# Ex_Adafruit_I2C_Adapter.net
KiCad netlist of a schematic drawn in EAGLE
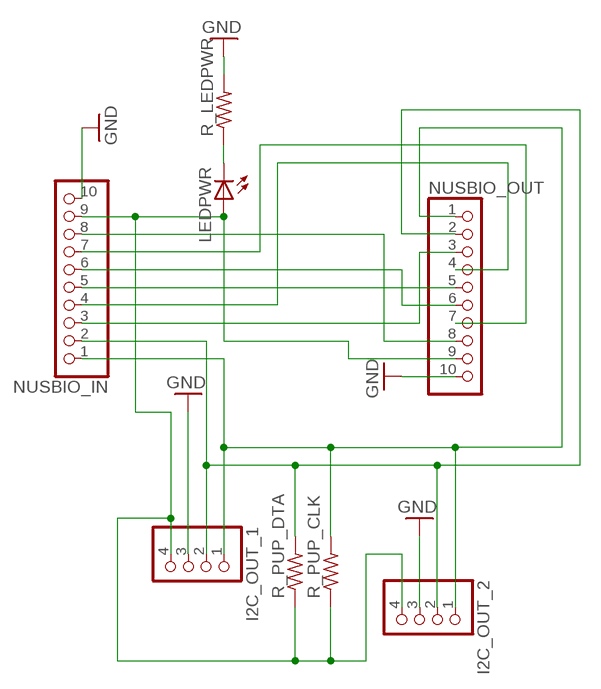
[diagram p0: schematic, sheet 1]

(export (version "E")
  (design (tool "Eeschema 10.0.6"))
  (components
    (comp (ref "I2C_OUT_1")
      (value "PINHD-1X4")
      (footprint "eagle-import:1X04")
      (libsource (lib "eagle-import") (part "PINHD-1X4"))
    )
    (comp (ref "I2C_OUT_2")
      (value "PINHD-1X4")
      (footprint "eagle-import:1X04")
      (libsource (lib "eagle-import") (part "PINHD-1X4"))
    )
    (comp (ref "LEDPWR")
      (value "LEDCHIPLED_0805")
      (footprint "eagle-import:CHIPLED_0805")
      (libsource (lib "eagle-import") (part "LEDCHIPLED_0805"))
    )
    (comp (ref "NUSBIO_IN")
      (value "PINHD-1X10")
      (footprint "eagle-import:1X10-BIG")
      (libsource (lib "eagle-import") (part "PINHD-1X10"))
    )
    (comp (ref "NUSBIO_OUT")
      (value "PINHD-1X10")
      (footprint "eagle-import:1X10-BIG")
      (libsource (lib "eagle-import") (part "PINHD-1X10"))
    )
    (comp (ref "R_LEDPWR")
      (value "R-US_R0805")
      (footprint "eagle-import:R0805")
      (libsource (lib "eagle-import") (part "R-US_R0805"))
    )
    (comp (ref "R_PUP_CLK")
      (value "R-US_R0805")
      (footprint "eagle-import:R0805")
      (libsource (lib "eagle-import") (part "R-US_R0805"))
    )
    (comp (ref "R_PUP_DTA")
      (value "R-US_R0805")
      (footprint "eagle-import:R0805")
      (libsource (lib "eagle-import") (part "R-US_R0805"))
    )
  )
  (nets
    (net (code "1") (name "GND") (class "Default")
      (node (ref "I2C_OUT_1") (pin "3") (pinfunction "3_3") (pintype "passive"))
      (node (ref "I2C_OUT_2") (pin "3") (pinfunction "3_3") (pintype "passive"))
      (node (ref "NUSBIO_IN") (pin "10") (pinfunction "10_10") (pintype "passive"))
      (node (ref "NUSBIO_OUT") (pin "10") (pinfunction "10_10") (pintype "passive"))
      (node (ref "R_LEDPWR") (pin "2") (pinfunction "2_2") (pintype "passive"))
    )
    (net (code "2") (name "Net-(I2C_OUT_1-Pad1)") (class "Default")
      (node (ref "I2C_OUT_1") (pin "1") (pinfunction "1_1") (pintype "passive"))
      (node (ref "I2C_OUT_2") (pin "1") (pinfunction "1_1") (pintype "passive"))
      (node (ref "NUSBIO_IN") (pin "1") (pinfunction "1_1") (pintype "passive"))
      (node (ref "NUSBIO_OUT") (pin "1") (pinfunction "1_1") (pintype "passive"))
      (node (ref "R_PUP_CLK") (pin "2") (pinfunction "2_2") (pintype "passive"))
    )
    (net (code "3") (name "Net-(I2C_OUT_1-Pad2)") (class "Default")
      (node (ref "I2C_OUT_1") (pin "2") (pinfunction "2_2") (pintype "passive"))
      (node (ref "I2C_OUT_2") (pin "2") (pinfunction "2_2") (pintype "passive"))
      (node (ref "NUSBIO_IN") (pin "2") (pinfunction "2_2") (pintype "passive"))
      (node (ref "NUSBIO_OUT") (pin "2") (pinfunction "2_2") (pintype "passive"))
      (node (ref "R_PUP_DTA") (pin "2") (pinfunction "2_2") (pintype "passive"))
    )
    (net (code "4") (name "Net-(I2C_OUT_1-Pad4)") (class "Default")
      (node (ref "I2C_OUT_1") (pin "4") (pinfunction "4_4") (pintype "passive"))
      (node (ref "I2C_OUT_2") (pin "4") (pinfunction "4_4") (pintype "passive"))
      (node (ref "LEDPWR") (pin "A") (pinfunction "A_A") (pintype "passive"))
      (node (ref "NUSBIO_IN") (pin "9") (pinfunction "9_9") (pintype "passive"))
      (node (ref "NUSBIO_OUT") (pin "9") (pinfunction "9_9") (pintype "passive"))
      (node (ref "R_PUP_CLK") (pin "1") (pinfunction "1_1") (pintype "passive"))
      (node (ref "R_PUP_DTA") (pin "1") (pinfunction "1_1") (pintype "passive"))
    )
    (net (code "5") (name "Net-(LEDPWR-PadC)") (class "Default")
      (node (ref "LEDPWR") (pin "C") (pinfunction "C_C") (pintype "passive"))
      (node (ref "R_LEDPWR") (pin "1") (pinfunction "1_1") (pintype "passive"))
    )
    (net (code "6") (name "Net-(NUSBIO_IN-Pad3)") (class "Default")
      (node (ref "NUSBIO_IN") (pin "3") (pinfunction "3_3") (pintype "passive"))
      (node (ref "NUSBIO_OUT") (pin "3") (pinfunction "3_3") (pintype "passive"))
    )
    (net (code "7") (name "Net-(NUSBIO_IN-Pad4)") (class "Default")
      (node (ref "NUSBIO_IN") (pin "4") (pinfunction "4_4") (pintype "passive"))
      (node (ref "NUSBIO_OUT") (pin "4") (pinfunction "4_4") (pintype "passive"))
    )
    (net (code "8") (name "Net-(NUSBIO_IN-Pad5)") (class "Default")
      (node (ref "NUSBIO_IN") (pin "5") (pinfunction "5_5") (pintype "passive"))
      (node (ref "NUSBIO_OUT") (pin "5") (pinfunction "5_5") (pintype "passive"))
    )
    (net (code "9") (name "Net-(NUSBIO_IN-Pad6)") (class "Default")
      (node (ref "NUSBIO_IN") (pin "6") (pinfunction "6_6") (pintype "passive"))
      (node (ref "NUSBIO_OUT") (pin "6") (pinfunction "6_6") (pintype "passive"))
    )
    (net (code "10") (name "Net-(NUSBIO_IN-Pad7)") (class "Default")
      (node (ref "NUSBIO_IN") (pin "7") (pinfunction "7_7") (pintype "passive"))
      (node (ref "NUSBIO_OUT") (pin "7") (pinfunction "7_7") (pintype "passive"))
    )
    (net (code "11") (name "Net-(NUSBIO_IN-Pad8)") (class "Default")
      (node (ref "NUSBIO_IN") (pin "8") (pinfunction "8_8") (pintype "passive"))
      (node (ref "NUSBIO_OUT") (pin "8") (pinfunction "8_8") (pintype "passive"))
    )
  )
)
